# A7_JTAG_CONFIG.net
KiCad netlist of a schematic drawn in Altium Designer
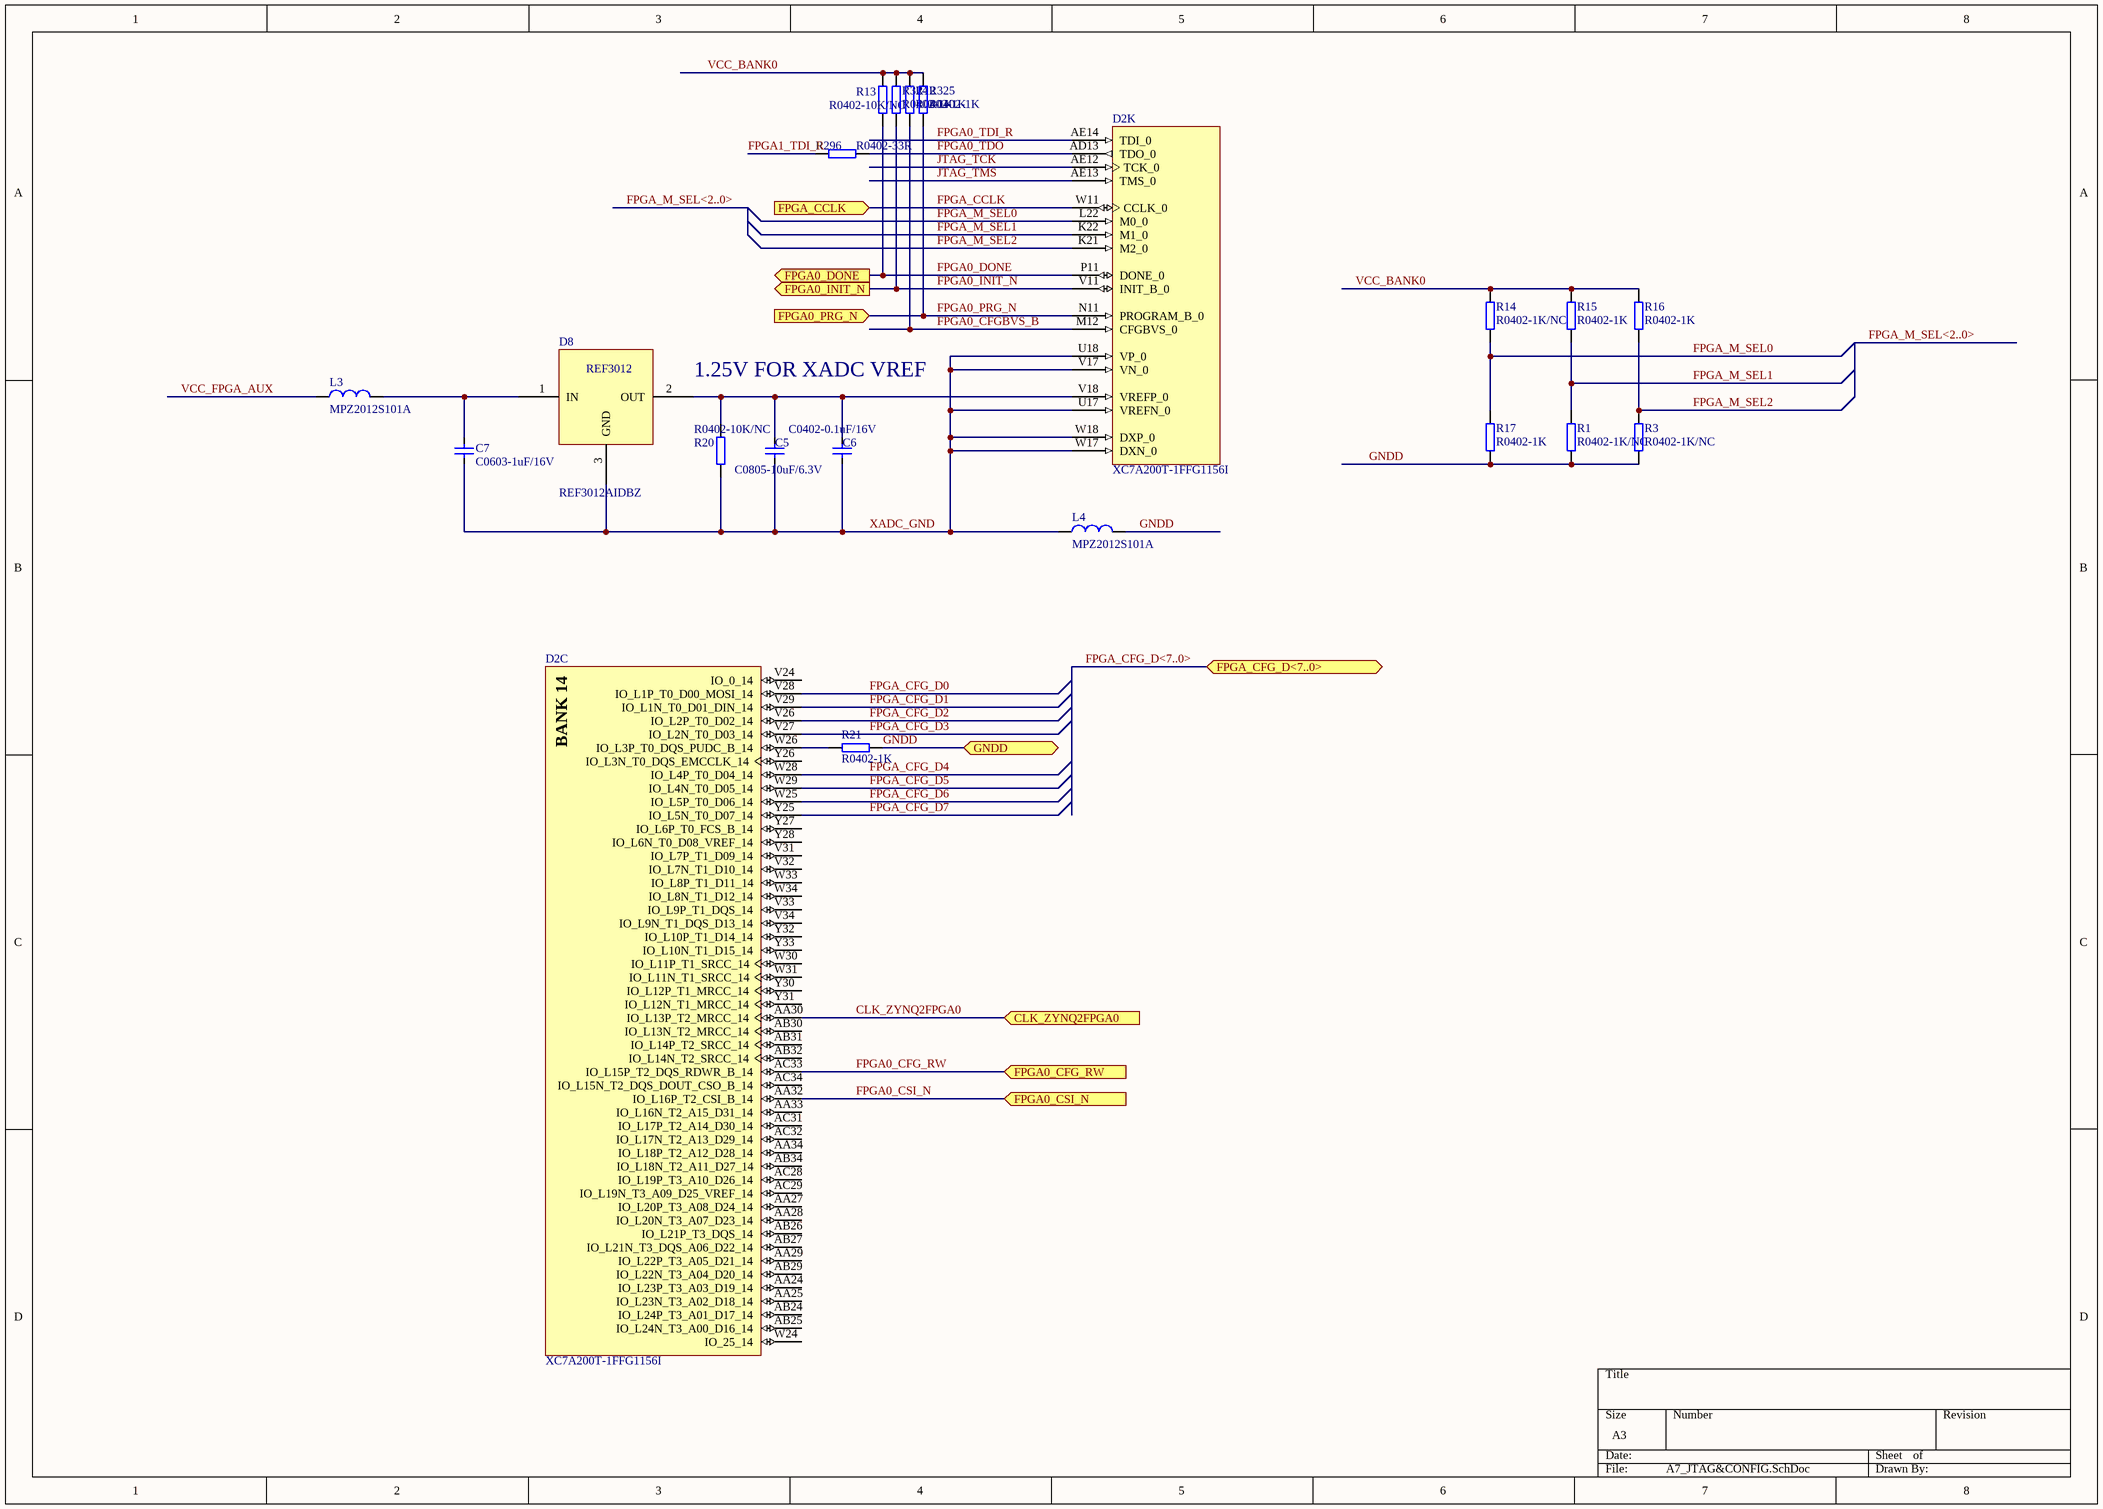
[diagram p0: A7_JTAG&CONFIG.SchDoc]

(export (version "E")
  (design (tool "Eeschema 10.0.6"))
  (components
    (comp (ref "C5")
      (value "C0805-10uF/6.3V")
      (footprint "C0805")
      (fields (field (name "SCHEMATIC_PART") "CAP"))
      (libsource (lib "Database_Libs1") (part "CAP"))
    )
    (comp (ref "C6")
      (value "C0402-0.1uF/16V")
      (footprint "C0402")
      (description "X7R")
      (fields (field (name "SCHEMATIC_PART") "CAP") (field (name "MANUFACTURER") "SAMSUNG"))
      (libsource (lib "Database_Libs1") (part "CAP"))
    )
    (comp (ref "C7")
      (value "C0603-1uF/16V")
      (footprint "C0603")
      (description "X7R")
      (fields (field (name "SCHEMATIC_PART") "CAP"))
      (libsource (lib "Database_Libs1") (part "CAP"))
    )
    (comp (ref "D2")
      (value "XC7A200T-1FFG1156I")
      (footprint "FFG1156")
      (description "Artix-7 FPGA, 500 User I/Os, 16 GTP, 1156-Ball BGA, Speed Grade 1, Industrial Grade, Pb-Free")
      (fields (field (name "GENERIC PART NUMBER") "XC7A200T") (field (name "MANUFACTURER") "Xilinx"))
      (libsource (lib "Xilinx Artix-7") (part "XC7A200T-1FFG1156I"))
    )
    (comp (ref "D8") (value "REF3012AIDBZ") (footprint "SOT-23") (libsource (lib "SCHLIB1") (part "REF3012")))
    (comp (ref "L3")
      (value "MPZ2012S101A")
      (footprint "R0805")
      (fields (field (name "SCHEMATIC_PART") "BEAD") (field (name "MANUFACTURER") "TDK"))
      (libsource (lib "Database_Libs1") (part "BEAD"))
    )
    (comp (ref "L4")
      (value "MPZ2012S101A")
      (footprint "R0805")
      (fields (field (name "SCHEMATIC_PART") "BEAD") (field (name "MANUFACTURER") "TDK"))
      (libsource (lib "Database_Libs1") (part "BEAD"))
    )
    (comp (ref "R1")
      (value "R0402-1K/NC")
      (footprint "R0402")
      (fields (field (name "SCHEMATIC_PART") "RES") (field (name "MANUFACTURER") "SAMSUNG"))
      (libsource (lib "Database_Libs1") (part "RES"))
    )
    (comp (ref "R3")
      (value "R0402-1K/NC")
      (footprint "R0402")
      (fields (field (name "SCHEMATIC_PART") "RES") (field (name "MANUFACTURER") "SAMSUNG"))
      (libsource (lib "Database_Libs1") (part "RES"))
    )
    (comp (ref "R12")
      (value "R0402-1K")
      (footprint "R0402")
      (fields (field (name "SCHEMATIC_PART") "RES") (field (name "MANUFACTURER") "SAMSUNG"))
      (libsource (lib "Database_Libs1") (part "RES"))
    )
    (comp (ref "R13")
      (value "R0402-10K/NC")
      (footprint "R0402")
      (fields (field (name "SCHEMATIC_PART") "RES") (field (name "MANUFACTURER") "SAMSUNG"))
      (libsource (lib "Database_Libs1") (part "RES"))
    )
    (comp (ref "R14")
      (value "R0402-1K/NC")
      (footprint "R0402")
      (fields (field (name "SCHEMATIC_PART") "RES") (field (name "MANUFACTURER") "SAMSUNG"))
      (libsource (lib "Database_Libs1") (part "RES"))
    )
    (comp (ref "R15")
      (value "R0402-1K")
      (footprint "R0402")
      (fields (field (name "SCHEMATIC_PART") "RES") (field (name "MANUFACTURER") "SAMSUNG"))
      (libsource (lib "Database_Libs1") (part "RES"))
    )
    (comp (ref "R16")
      (value "R0402-1K")
      (footprint "R0402")
      (fields (field (name "SCHEMATIC_PART") "RES") (field (name "MANUFACTURER") "SAMSUNG"))
      (libsource (lib "Database_Libs1") (part "RES"))
    )
    (comp (ref "R17")
      (value "R0402-1K")
      (footprint "R0402")
      (fields (field (name "SCHEMATIC_PART") "RES") (field (name "MANUFACTURER") "SAMSUNG"))
      (libsource (lib "Database_Libs1") (part "RES"))
    )
    (comp (ref "R20")
      (value "R0402-10K/NC")
      (footprint "R0402")
      (fields (field (name "SCHEMATIC_PART") "RES") (field (name "MANUFACTURER") "SAMSUNG"))
      (libsource (lib "Database_Libs1") (part "RES"))
    )
    (comp (ref "R21")
      (value "R0402-1K")
      (footprint "R0402")
      (fields (field (name "SCHEMATIC_PART") "RES") (field (name "MANUFACTURER") "SAMSUNG"))
      (libsource (lib "Database_Libs1") (part "RES"))
    )
    (comp (ref "R296")
      (value "R0402-33R")
      (footprint "R0402")
      (fields (field (name "SCHEMATIC_PART") "RES") (field (name "MANUFACTURER") "SAMSUNG"))
      (libsource (lib "Database_Libs1") (part "RES"))
    )
    (comp (ref "R324")
      (value "R0402-1K")
      (footprint "R0402")
      (fields (field (name "SCHEMATIC_PART") "RES") (field (name "MANUFACTURER") "SAMSUNG"))
      (libsource (lib "Database_Libs1") (part "RES"))
    )
    (comp (ref "R325")
      (value "R0402-1K")
      (footprint "R0402")
      (fields (field (name "SCHEMATIC_PART") "RES") (field (name "MANUFACTURER") "SAMSUNG"))
      (libsource (lib "Database_Libs1") (part "RES"))
    )
  )
  (nets
    (net (code "3") (name "/CLK_ZYNQ2FPGA0") (class "Default")
      (node (ref "D2") (pin "AA30") (pinfunction "IO_L13P_T2_MRCC_14_AA30") (pintype "bidirectional"))
    )
    (net (code "4") (name "/FPGA0_CFGBVS_B") (class "Default")
      (node (ref "D2") (pin "M12") (pinfunction "CFGBVS_0_M12") (pintype "input"))
      (node (ref "R12") (pin "1") (pintype "passive"))
    )
    (net (code "5") (name "/FPGA0_CFG_RW") (class "Default")
      (node (ref "D2") (pin "AC33") (pinfunction "IO_L15P_T2_DQS_RDWR_B_14_AC33") (pintype "bidirectional"))
    )
    (net (code "6") (name "/FPGA0_CSI_N") (class "Default")
      (node (ref "D2") (pin "AA32") (pinfunction "IO_L16P_T2_CSI_B_14_AA32") (pintype "bidirectional"))
    )
    (net (code "7") (name "/FPGA0_DONE") (class "Default")
      (node (ref "D2") (pin "P11") (pinfunction "DONE_0_P11") (pintype "bidirectional"))
      (node (ref "R13") (pin "1") (pintype "passive"))
    )
    (net (code "8") (name "/FPGA0_INIT_N") (class "Default")
      (node (ref "D2") (pin "V11") (pinfunction "INIT_B_0_V11") (pintype "bidirectional"))
      (node (ref "R324") (pin "1") (pintype "passive"))
    )
    (net (code "9") (name "/FPGA0_PRG_N") (class "Default")
      (node (ref "D2") (pin "N11") (pinfunction "PROGRAM_B_0_N11") (pintype "input"))
      (node (ref "R325") (pin "1") (pintype "passive"))
    )
    (net (code "10") (name "/FPGA0_TDI_R") (class "Default")
      (node (ref "D2") (pin "AE14") (pinfunction "TDI_0_AE14") (pintype "input"))
    )
    (net (code "11") (name "/FPGA0_TDO") (class "Default")
      (node (ref "D2") (pin "AD13") (pinfunction "TDO_0_AD13") (pintype "output"))
      (node (ref "R296") (pin "2") (pintype "passive"))
    )
    (net (code "12") (name "/FPGA1_TDI_R") (class "Default")
      (node (ref "R296") (pin "1") (pintype "passive"))
    )
    (net (code "13") (name "/FPGA_CCLK") (class "Default")
      (node (ref "D2") (pin "W11") (pinfunction "CCLK_0_W11") (pintype "bidirectional"))
    )
    (net (code "14") (name "/FPGA_CFG_D0") (class "Default")
      (node (ref "D2") (pin "V28") (pinfunction "IO_L1P_T0_D00_MOSI_14_V28") (pintype "bidirectional"))
    )
    (net (code "15") (name "/FPGA_CFG_D1") (class "Default")
      (node (ref "D2") (pin "V29") (pinfunction "IO_L1N_T0_D01_DIN_14_V29") (pintype "bidirectional"))
    )
    (net (code "16") (name "/FPGA_CFG_D2") (class "Default")
      (node (ref "D2") (pin "V26") (pinfunction "IO_L2P_T0_D02_14_V26") (pintype "bidirectional"))
    )
    (net (code "17") (name "/FPGA_CFG_D3") (class "Default")
      (node (ref "D2") (pin "V27") (pinfunction "IO_L2N_T0_D03_14_V27") (pintype "bidirectional"))
    )
    (net (code "18") (name "/FPGA_CFG_D4") (class "Default")
      (node (ref "D2") (pin "W28") (pinfunction "IO_L4P_T0_D04_14_W28") (pintype "bidirectional"))
    )
    (net (code "19") (name "/FPGA_CFG_D5") (class "Default")
      (node (ref "D2") (pin "W29") (pinfunction "IO_L4N_T0_D05_14_W29") (pintype "bidirectional"))
    )
    (net (code "20") (name "/FPGA_CFG_D6") (class "Default")
      (node (ref "D2") (pin "W25") (pinfunction "IO_L5P_T0_D06_14_W25") (pintype "bidirectional"))
    )
    (net (code "21") (name "/FPGA_CFG_D7") (class "Default")
      (node (ref "D2") (pin "Y25") (pinfunction "IO_L5N_T0_D07_14_Y25") (pintype "bidirectional"))
    )
    (net (code "22") (name "/FPGA_M_SEL0") (class "Default")
      (node (ref "D2") (pin "L22") (pinfunction "M0_0_L22") (pintype "input"))
      (node (ref "R14") (pin "1") (pintype "passive"))
      (node (ref "R17") (pin "2") (pintype "passive"))
    )
    (net (code "23") (name "/FPGA_M_SEL1") (class "Default")
      (node (ref "D2") (pin "K22") (pinfunction "M1_0_K22") (pintype "input"))
      (node (ref "R1") (pin "2") (pintype "passive"))
      (node (ref "R15") (pin "1") (pintype "passive"))
    )
    (net (code "24") (name "/FPGA_M_SEL2") (class "Default")
      (node (ref "D2") (pin "K21") (pinfunction "M2_0_K21") (pintype "input"))
      (node (ref "R16") (pin "1") (pintype "passive"))
      (node (ref "R3") (pin "2") (pintype "passive"))
    )
    (net (code "25") (name "/GNDD") (class "Default")
      (node (ref "L4") (pin "2") (pinfunction "2_2") (pintype "passive"))
      (node (ref "R1") (pin "1") (pintype "passive"))
      (node (ref "R17") (pin "1") (pintype "passive"))
      (node (ref "R21") (pin "1") (pintype "passive"))
      (node (ref "R3") (pin "1") (pintype "passive"))
    )
    (net (code "26") (name "/JTAG_TCK") (class "Default")
      (node (ref "D2") (pin "AE12") (pinfunction "TCK_0_AE12") (pintype "input"))
    )
    (net (code "27") (name "/JTAG_TMS") (class "Default")
      (node (ref "D2") (pin "AE13") (pinfunction "TMS_0_AE13") (pintype "input"))
    )
    (net (code "28") (name "/VCC_BANK0") (class "Default")
      (node (ref "R12") (pin "2") (pintype "passive"))
      (node (ref "R13") (pin "2") (pintype "passive"))
      (node (ref "R14") (pin "2") (pintype "passive"))
      (node (ref "R15") (pin "2") (pintype "passive"))
      (node (ref "R16") (pin "2") (pintype "passive"))
      (node (ref "R324") (pin "2") (pintype "passive"))
      (node (ref "R325") (pin "2") (pintype "passive"))
    )
    (net (code "29") (name "/VCC_FPGA_AUX") (class "Default")
      (node (ref "L3") (pin "1") (pinfunction "1_1") (pintype "passive"))
    )
    (net (code "30") (name "/XADC_GND") (class "Default")
      (node (ref "C5") (pin "2") (pinfunction "2_2") (pintype "passive"))
      (node (ref "C6") (pin "2") (pinfunction "2_2") (pintype "passive"))
      (node (ref "C7") (pin "2") (pinfunction "2_2") (pintype "passive"))
      (node (ref "D2") (pin "U17") (pinfunction "VREFN_0_U17") (pintype "input"))
      (node (ref "D2") (pin "U18") (pinfunction "VP_0_U18") (pintype "input"))
      (node (ref "D2") (pin "V17") (pinfunction "VN_0_V17") (pintype "input"))
      (node (ref "D2") (pin "W17") (pinfunction "DXN_0_W17") (pintype "input"))
      (node (ref "D2") (pin "W18") (pinfunction "DXP_0_W18") (pintype "input"))
      (node (ref "D8") (pin "3") (pinfunction "GND_3") (pintype "passive"))
      (node (ref "L4") (pin "1") (pinfunction "1_1") (pintype "passive"))
      (node (ref "R20") (pin "2") (pintype "passive"))
    )
    (net (code "33") (name "Net-(D2C-IO_L3P_T0_DQS_PUDC_B_14)") (class "Default")
      (node (ref "D2") (pin "W26") (pinfunction "IO_L3P_T0_DQS_PUDC_B_14_W26") (pintype "bidirectional"))
      (node (ref "R21") (pin "2") (pintype "passive"))
    )
    (net (code "34") (name "Net-(D2K-VREFP_0)") (class "Default")
      (node (ref "C5") (pin "1") (pinfunction "1_1") (pintype "passive"))
      (node (ref "C6") (pin "1") (pinfunction "1_1") (pintype "passive"))
      (node (ref "D2") (pin "V18") (pinfunction "VREFP_0_V18") (pintype "input"))
      (node (ref "D8") (pin "2") (pinfunction "OUT_2") (pintype "passive"))
      (node (ref "R20") (pin "1") (pintype "passive"))
    )
    (net (code "35") (name "Net-(D8-IN)") (class "Default")
      (node (ref "C7") (pin "1") (pinfunction "1_1") (pintype "passive"))
      (node (ref "D8") (pin "1") (pinfunction "IN_1") (pintype "passive"))
      (node (ref "L3") (pin "2") (pinfunction "2_2") (pintype "passive"))
    )
    (net (code "36") (name "unconnected-(D2C-IO_0_14-PadV24)") (class "Default")
      (node (ref "D2") (pin "V24") (pinfunction "IO_0_14_V24") (pintype "bidirectional"))
    )
    (net (code "37") (name "unconnected-(D2C-IO_25_14-PadW24)") (class "Default")
      (node (ref "D2") (pin "W24") (pinfunction "IO_25_14_W24") (pintype "bidirectional"))
    )
    (net (code "38") (name "unconnected-(D2C-IO_L3N_T0_DQS_EMCCLK_14-PadY26)") (class "Default")
      (node (ref "D2") (pin "Y26") (pinfunction "IO_L3N_T0_DQS_EMCCLK_14_Y26") (pintype "bidirectional"))
    )
    (net (code "39") (name "unconnected-(D2C-IO_L6N_T0_D08_VREF_14-PadY28)") (class "Default")
      (node (ref "D2") (pin "Y28") (pinfunction "IO_L6N_T0_D08_VREF_14_Y28") (pintype "bidirectional"))
    )
    (net (code "40") (name "unconnected-(D2C-IO_L6P_T0_FCS_B_14-PadY27)") (class "Default")
      (node (ref "D2") (pin "Y27") (pinfunction "IO_L6P_T0_FCS_B_14_Y27") (pintype "bidirectional"))
    )
    (net (code "41") (name "unconnected-(D2C-IO_L7N_T1_D10_14-PadV32)") (class "Default")
      (node (ref "D2") (pin "V32") (pinfunction "IO_L7N_T1_D10_14_V32") (pintype "bidirectional"))
    )
    (net (code "42") (name "unconnected-(D2C-IO_L7P_T1_D09_14-PadV31)") (class "Default")
      (node (ref "D2") (pin "V31") (pinfunction "IO_L7P_T1_D09_14_V31") (pintype "bidirectional"))
    )
    (net (code "43") (name "unconnected-(D2C-IO_L8N_T1_D12_14-PadW34)") (class "Default")
      (node (ref "D2") (pin "W34") (pinfunction "IO_L8N_T1_D12_14_W34") (pintype "bidirectional"))
    )
    (net (code "44") (name "unconnected-(D2C-IO_L8P_T1_D11_14-PadW33)") (class "Default")
      (node (ref "D2") (pin "W33") (pinfunction "IO_L8P_T1_D11_14_W33") (pintype "bidirectional"))
    )
    (net (code "45") (name "unconnected-(D2C-IO_L9N_T1_DQS_D13_14-PadV34)") (class "Default")
      (node (ref "D2") (pin "V34") (pinfunction "IO_L9N_T1_DQS_D13_14_V34") (pintype "bidirectional"))
    )
    (net (code "46") (name "unconnected-(D2C-IO_L9P_T1_DQS_14-PadV33)") (class "Default")
      (node (ref "D2") (pin "V33") (pinfunction "IO_L9P_T1_DQS_14_V33") (pintype "bidirectional"))
    )
    (net (code "47") (name "unconnected-(D2C-IO_L10N_T1_D15_14-PadY33)") (class "Default")
      (node (ref "D2") (pin "Y33") (pinfunction "IO_L10N_T1_D15_14_Y33") (pintype "bidirectional"))
    )
    (net (code "48") (name "unconnected-(D2C-IO_L10P_T1_D14_14-PadY32)") (class "Default")
      (node (ref "D2") (pin "Y32") (pinfunction "IO_L10P_T1_D14_14_Y32") (pintype "bidirectional"))
    )
    (net (code "49") (name "unconnected-(D2C-IO_L11N_T1_SRCC_14-PadW31)") (class "Default")
      (node (ref "D2") (pin "W31") (pinfunction "IO_L11N_T1_SRCC_14_W31") (pintype "bidirectional"))
    )
    (net (code "50") (name "unconnected-(D2C-IO_L11P_T1_SRCC_14-PadW30)") (class "Default")
      (node (ref "D2") (pin "W30") (pinfunction "IO_L11P_T1_SRCC_14_W30") (pintype "bidirectional"))
    )
    (net (code "51") (name "unconnected-(D2C-IO_L12N_T1_MRCC_14-PadY31)") (class "Default")
      (node (ref "D2") (pin "Y31") (pinfunction "IO_L12N_T1_MRCC_14_Y31") (pintype "bidirectional"))
    )
    (net (code "52") (name "unconnected-(D2C-IO_L12P_T1_MRCC_14-PadY30)") (class "Default")
      (node (ref "D2") (pin "Y30") (pinfunction "IO_L12P_T1_MRCC_14_Y30") (pintype "bidirectional"))
    )
    (net (code "53") (name "unconnected-(D2C-IO_L13N_T2_MRCC_14-PadAB30)") (class "Default")
      (node (ref "D2") (pin "AB30") (pinfunction "IO_L13N_T2_MRCC_14_AB30") (pintype "bidirectional"))
    )
    (net (code "54") (name "unconnected-(D2C-IO_L14N_T2_SRCC_14-PadAB32)") (class "Default")
      (node (ref "D2") (pin "AB32") (pinfunction "IO_L14N_T2_SRCC_14_AB32") (pintype "bidirectional"))
    )
    (net (code "55") (name "unconnected-(D2C-IO_L14P_T2_SRCC_14-PadAB31)") (class "Default")
      (node (ref "D2") (pin "AB31") (pinfunction "IO_L14P_T2_SRCC_14_AB31") (pintype "bidirectional"))
    )
    (net (code "56") (name "unconnected-(D2C-IO_L15N_T2_DQS_DOUT_CSO_B_14-PadAC34)") (class "Default")
      (node (ref "D2") (pin "AC34") (pinfunction "IO_L15N_T2_DQS_DOUT_CSO_B_14_AC34") (pintype "bidirectional"))
    )
    (net (code "57") (name "unconnected-(D2C-IO_L16N_T2_A15_D31_14-PadAA33)") (class "Default")
      (node (ref "D2") (pin "AA33") (pinfunction "IO_L16N_T2_A15_D31_14_AA33") (pintype "bidirectional"))
    )
    (net (code "58") (name "unconnected-(D2C-IO_L17N_T2_A13_D29_14-PadAC32)") (class "Default")
      (node (ref "D2") (pin "AC32") (pinfunction "IO_L17N_T2_A13_D29_14_AC32") (pintype "bidirectional"))
    )
    (net (code "59") (name "unconnected-(D2C-IO_L17P_T2_A14_D30_14-PadAC31)") (class "Default")
      (node (ref "D2") (pin "AC31") (pinfunction "IO_L17P_T2_A14_D30_14_AC31") (pintype "bidirectional"))
    )
    (net (code "60") (name "unconnected-(D2C-IO_L18N_T2_A11_D27_14-PadAB34)") (class "Default")
      (node (ref "D2") (pin "AB34") (pinfunction "IO_L18N_T2_A11_D27_14_AB34") (pintype "bidirectional"))
    )
    (net (code "61") (name "unconnected-(D2C-IO_L18P_T2_A12_D28_14-PadAA34)") (class "Default")
      (node (ref "D2") (pin "AA34") (pinfunction "IO_L18P_T2_A12_D28_14_AA34") (pintype "bidirectional"))
    )
    (net (code "62") (name "unconnected-(D2C-IO_L19N_T3_A09_D25_VREF_14-PadAC29)") (class "Default")
      (node (ref "D2") (pin "AC29") (pinfunction "IO_L19N_T3_A09_D25_VREF_14_AC29") (pintype "bidirectional"))
    )
    (net (code "63") (name "unconnected-(D2C-IO_L19P_T3_A10_D26_14-PadAC28)") (class "Default")
      (node (ref "D2") (pin "AC28") (pinfunction "IO_L19P_T3_A10_D26_14_AC28") (pintype "bidirectional"))
    )
    (net (code "64") (name "unconnected-(D2C-IO_L20N_T3_A07_D23_14-PadAA28)") (class "Default")
      (node (ref "D2") (pin "AA28") (pinfunction "IO_L20N_T3_A07_D23_14_AA28") (pintype "bidirectional"))
    )
    (net (code "65") (name "unconnected-(D2C-IO_L20P_T3_A08_D24_14-PadAA27)") (class "Default")
      (node (ref "D2") (pin "AA27") (pinfunction "IO_L20P_T3_A08_D24_14_AA27") (pintype "bidirectional"))
    )
    (net (code "66") (name "unconnected-(D2C-IO_L21N_T3_DQS_A06_D22_14-PadAB27)") (class "Default")
      (node (ref "D2") (pin "AB27") (pinfunction "IO_L21N_T3_DQS_A06_D22_14_AB27") (pintype "bidirectional"))
    )
    (net (code "67") (name "unconnected-(D2C-IO_L21P_T3_DQS_14-PadAB26)") (class "Default")
      (node (ref "D2") (pin "AB26") (pinfunction "IO_L21P_T3_DQS_14_AB26") (pintype "bidirectional"))
    )
    (net (code "68") (name "unconnected-(D2C-IO_L22N_T3_A04_D20_14-PadAB29)") (class "Default")
      (node (ref "D2") (pin "AB29") (pinfunction "IO_L22N_T3_A04_D20_14_AB29") (pintype "bidirectional"))
    )
    (net (code "69") (name "unconnected-(D2C-IO_L22P_T3_A05_D21_14-PadAA29)") (class "Default")
      (node (ref "D2") (pin "AA29") (pinfunction "IO_L22P_T3_A05_D21_14_AA29") (pintype "bidirectional"))
    )
    (net (code "70") (name "unconnected-(D2C-IO_L23N_T3_A02_D18_14-PadAA25)") (class "Default")
      (node (ref "D2") (pin "AA25") (pinfunction "IO_L23N_T3_A02_D18_14_AA25") (pintype "bidirectional"))
    )
    (net (code "71") (name "unconnected-(D2C-IO_L23P_T3_A03_D19_14-PadAA24)") (class "Default")
      (node (ref "D2") (pin "AA24") (pinfunction "IO_L23P_T3_A03_D19_14_AA24") (pintype "bidirectional"))
    )
    (net (code "72") (name "unconnected-(D2C-IO_L24N_T3_A00_D16_14-PadAB25)") (class "Default")
      (node (ref "D2") (pin "AB25") (pinfunction "IO_L24N_T3_A00_D16_14_AB25") (pintype "bidirectional"))
    )
    (net (code "73") (name "unconnected-(D2C-IO_L24P_T3_A01_D17_14-PadAB24)") (class "Default")
      (node (ref "D2") (pin "AB24") (pinfunction "IO_L24P_T3_A01_D17_14_AB24") (pintype "bidirectional"))
    )
  )
)
